# Arduino__Connectors.net
KiCad netlist of a schematic drawn in Altium Designer
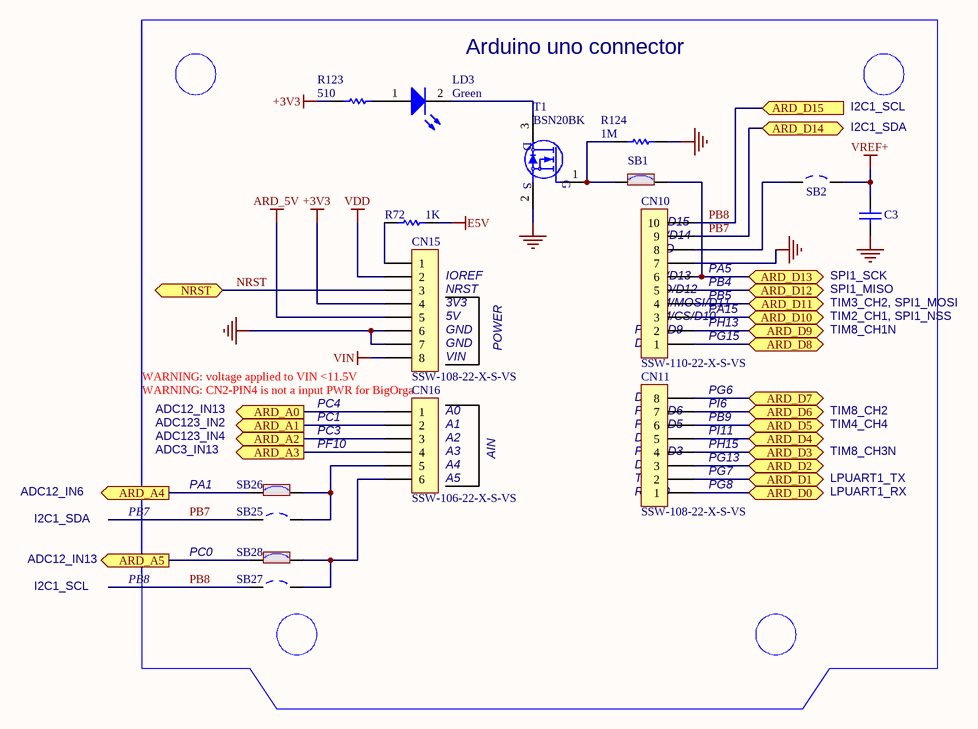
[diagram p0: Arduino_ Connectors.SchDoc]

(export (version "E")
  (design (tool "Eeschema 10.0.6"))
  (components
    (comp (ref "C3")
      (value "~")
      (footprint "0603C")
      (description "Capacitor,100nF,10%,16V,X7R,0603,YAGEO")
      (fields (field (name "PUBLISHER") "Altium Limited"))
      (libsource (lib "Miscellaneous Devices") (part "Cap"))
    )
    (comp (ref "CN10")
      (value "SSW-110-22-X-S-VS")
      (footprint "SSW-110-22-X-S-VS")
      (description "Header, 10-Pin, Single row,female")
      (fields (field (name "PUBLISHER") "Altium Limited"))
      (libsource (lib "Nucleo_64") (part "Header 10X1_Female"))
    )
    (comp (ref "CN11")
      (value "SSW-108-22-X-S-VS")
      (footprint "SSW-108-22-X-S-VS")
      (description "Header, 8-Pin, Single row,female")
      (fields (field (name "PUBLISHER") "Altium Limited"))
      (libsource (lib "Nucleo_64") (part "Header 8X1_Female"))
    )
    (comp (ref "CN15")
      (value "SSW-108-22-X-S-VS")
      (footprint "SSW-108-22-X-S-VS")
      (description "Header, 8-Pin, Single row,female")
      (fields (field (name "PUBLISHER") "Altium Limited"))
      (libsource (lib "") (part "Header 8X1_Female_1"))
    )
    (comp (ref "CN16")
      (value "SSW-106-22-X-S-VS")
      (footprint "SSW-106-22-X-S-VS")
      (description "Header, 6-Pin, Single row,female")
      (fields (field (name "PUBLISHER") "Altium Limited"))
      (libsource (lib "Nucleo_64") (part "Header 6X1_Female"))
    )
    (comp (ref "LD3")
      (value "19-213SY6C/S530-E2/TR8LED")
      (footprint "0603D")
      (description "LED,Green,0603")
      (fields (field (name "CORLOR") "Green") (field (name "PUBLISHER") "Altium Limited"))
      (libsource (lib "Miscellaneous Devices") (part "LED2"))
    )
    (comp (ref "R72")
      (value "1K")
      (footprint "0603R")
      (description "Resistor,1K,0603,1%")
      (fields (field (name "PUBLISHER") "Altium Limited"))
      (libsource (lib "Miscellaneous Devices") (part "res1"))
    )
    (comp (ref "R123")
      (value "510")
      (footprint "0603R")
      (description "Resistor, 510R , 0603,1%,YAGEO")
      (fields (field (name "Comment") "RC0603JR-07510RL") (field (name "PUBLISHER") "Altium Limited"))
      (libsource (lib "Miscellaneous Devices") (part "res1"))
    )
    (comp (ref "R124")
      (value "1M")
      (footprint "0603R")
      (description "Resistor, 1M , 0603")
      (fields (field (name "PUBLISHER") "Altium Limited"))
      (libsource (lib "Miscellaneous Devices") (part "res1"))
    )
    (comp (ref "SB1")
      (value "Solder Bridge ON")
      (footprint "SB_0603")
      (libsource (lib "MCD_TOOLS") (part "SB_ON"))
    )
    (comp (ref "SB2")
      (value "Solder Bridge OFF")
      (footprint "SB_0603")
      (libsource (lib "MCD_TOOLS") (part "SB_OFF"))
    )
    (comp (ref "SB25")
      (value "Solder Bridge OFF")
      (footprint "SB_0603")
      (libsource (lib "MCD_TOOLS") (part "SB_OFF"))
    )
    (comp (ref "SB26")
      (value "Solder Bridge ON")
      (footprint "SB_0603")
      (libsource (lib "MCD_TOOLS") (part "SB_ON"))
    )
    (comp (ref "SB27")
      (value "Solder Bridge OFF")
      (footprint "SB_0603")
      (libsource (lib "MCD_TOOLS") (part "SB_OFF"))
    )
    (comp (ref "SB28")
      (value "Solder Bridge ON")
      (footprint "SB_0603")
      (libsource (lib "MCD_TOOLS") (part "SB_ON"))
    )
    (comp (ref "T1") (value "BSN20BK") (footprint "SOT-23") (libsource (lib "MB525") (part "2N7000")))
  )
  (nets
    (net (code "1") (name "+3V3") (class "Default")
      (node (ref "CN15") (pin "4") (pinfunction "4_4") (pintype "passive"))
      (node (ref "R123") (pin "1") (pinfunction "1_1") (pintype "passive"))
    )
    (net (code "2") (name "/ARD_A0") (class "Default")
      (node (ref "CN16") (pin "1") (pinfunction "1_1") (pintype "passive"))
    )
    (net (code "3") (name "/ARD_A1") (class "Default")
      (node (ref "CN16") (pin "2") (pinfunction "2_2") (pintype "passive"))
    )
    (net (code "4") (name "/ARD_A2") (class "Default")
      (node (ref "CN16") (pin "3") (pinfunction "3_3") (pintype "passive"))
    )
    (net (code "5") (name "/ARD_A3") (class "Default")
      (node (ref "CN16") (pin "4") (pinfunction "4_4") (pintype "passive"))
    )
    (net (code "6") (name "/ARD_A4") (class "Default")
      (node (ref "SB26") (pin "1") (pinfunction "1_1") (pintype "passive"))
    )
    (net (code "7") (name "/ARD_A5") (class "Default")
      (node (ref "SB28") (pin "1") (pinfunction "1_1") (pintype "passive"))
    )
    (net (code "8") (name "/ARD_D0") (class "Default")
      (node (ref "CN11") (pin "1") (pinfunction "1_1") (pintype "passive"))
    )
    (net (code "9") (name "/ARD_D1") (class "Default")
      (node (ref "CN11") (pin "2") (pinfunction "2_2") (pintype "passive"))
    )
    (net (code "10") (name "/ARD_D2") (class "Default")
      (node (ref "CN11") (pin "3") (pinfunction "3_3") (pintype "passive"))
    )
    (net (code "11") (name "/ARD_D3") (class "Default")
      (node (ref "CN11") (pin "4") (pinfunction "4_4") (pintype "passive"))
    )
    (net (code "12") (name "/ARD_D4") (class "Default")
      (node (ref "CN11") (pin "5") (pinfunction "5_5") (pintype "passive"))
    )
    (net (code "13") (name "/ARD_D5") (class "Default")
      (node (ref "CN11") (pin "6") (pinfunction "6_6") (pintype "passive"))
    )
    (net (code "14") (name "/ARD_D6") (class "Default")
      (node (ref "CN11") (pin "7") (pinfunction "7_7") (pintype "passive"))
    )
    (net (code "15") (name "/ARD_D7") (class "Default")
      (node (ref "CN11") (pin "8") (pinfunction "8_8") (pintype "passive"))
    )
    (net (code "16") (name "/ARD_D8") (class "Default")
      (node (ref "CN10") (pin "1") (pinfunction "1_1") (pintype "passive"))
    )
    (net (code "17") (name "/ARD_D9") (class "Default")
      (node (ref "CN10") (pin "2") (pinfunction "2_2") (pintype "passive"))
    )
    (net (code "18") (name "/ARD_D10") (class "Default")
      (node (ref "CN10") (pin "3") (pinfunction "3_3") (pintype "passive"))
    )
    (net (code "19") (name "/ARD_D11") (class "Default")
      (node (ref "CN10") (pin "4") (pinfunction "4_4") (pintype "passive"))
    )
    (net (code "20") (name "/ARD_D12") (class "Default")
      (node (ref "CN10") (pin "5") (pinfunction "5_5") (pintype "passive"))
    )
    (net (code "21") (name "/ARD_D13") (class "Default")
      (node (ref "CN10") (pin "6") (pinfunction "6_6") (pintype "passive"))
      (node (ref "SB1") (pin "2") (pinfunction "2_2") (pintype "passive"))
    )
    (net (code "22") (name "/NRST") (class "Default")
      (node (ref "CN15") (pin "3") (pinfunction "3_3") (pintype "passive"))
    )
    (net (code "23") (name "/PB7") (class "Default")
      (node (ref "CN10") (pin "9") (pinfunction "9_9") (pintype "passive"))
      (node (ref "SB25") (pin "1") (pinfunction "1_1") (pintype "passive"))
    )
    (net (code "24") (name "/PB8") (class "Default")
      (node (ref "CN10") (pin "10") (pinfunction "10_10") (pintype "passive"))
      (node (ref "SB27") (pin "1") (pinfunction "1_1") (pintype "passive"))
    )
    (net (code "25") (name "ARD_5V") (class "Default")
      (node (ref "CN15") (pin "5") (pinfunction "5_5") (pintype "passive"))
    )
    (net (code "26") (name "E5V") (class "Default")
      (node (ref "R72") (pin "1") (pinfunction "1_1") (pintype "passive"))
    )
    (net (code "27") (name "GND") (class "Default")
      (node (ref "C3") (pin "2") (pinfunction "2_2") (pintype "passive"))
      (node (ref "CN10") (pin "7") (pinfunction "7_7") (pintype "passive"))
      (node (ref "CN15") (pin "6") (pinfunction "6_6") (pintype "passive"))
      (node (ref "CN15") (pin "7") (pinfunction "7_7") (pintype "passive"))
      (node (ref "R124") (pin "2") (pinfunction "2_2") (pintype "passive"))
      (node (ref "T1") (pin "2") (pinfunction "S_2") (pintype "passive"))
    )
    (net (code "28") (name "Net-(CN10-Pad8)") (class "Default")
      (node (ref "CN10") (pin "8") (pinfunction "8_8") (pintype "passive"))
      (node (ref "SB2") (pin "1") (pinfunction "1_1") (pintype "passive"))
    )
    (net (code "29") (name "Net-(CN15-Pad1)") (class "Default")
      (node (ref "CN15") (pin "1") (pinfunction "1_1") (pintype "passive"))
      (node (ref "R72") (pin "2") (pinfunction "2_2") (pintype "passive"))
    )
    (net (code "30") (name "Net-(CN16-Pad5)") (class "Default")
      (node (ref "CN16") (pin "5") (pinfunction "5_5") (pintype "passive"))
      (node (ref "SB25") (pin "2") (pinfunction "2_2") (pintype "passive"))
      (node (ref "SB26") (pin "2") (pinfunction "2_2") (pintype "passive"))
    )
    (net (code "31") (name "Net-(CN16-Pad6)") (class "Default")
      (node (ref "CN16") (pin "6") (pinfunction "6_6") (pintype "passive"))
      (node (ref "SB27") (pin "2") (pinfunction "2_2") (pintype "passive"))
      (node (ref "SB28") (pin "2") (pinfunction "2_2") (pintype "passive"))
    )
    (net (code "32") (name "Net-(LD3-A)") (class "Default")
      (node (ref "LD3") (pin "1") (pinfunction "A_1") (pintype "passive"))
      (node (ref "R123") (pin "2") (pinfunction "2_2") (pintype "passive"))
    )
    (net (code "33") (name "Net-(LD3-K)") (class "Default")
      (node (ref "LD3") (pin "2") (pinfunction "K_2") (pintype "passive"))
      (node (ref "T1") (pin "3") (pinfunction "D_3") (pintype "passive"))
    )
    (net (code "34") (name "Net-(T1-G)") (class "Default")
      (node (ref "R124") (pin "1") (pinfunction "1_1") (pintype "passive"))
      (node (ref "SB1") (pin "1") (pinfunction "1_1") (pintype "passive"))
      (node (ref "T1") (pin "1") (pinfunction "G_1") (pintype "passive"))
    )
    (net (code "35") (name "VDD") (class "Default")
      (node (ref "CN15") (pin "2") (pinfunction "2_2") (pintype "passive"))
    )
    (net (code "36") (name "VIN") (class "Default")
      (node (ref "CN15") (pin "8") (pinfunction "8_8") (pintype "passive"))
    )
    (net (code "37") (name "VREF+") (class "Default")
      (node (ref "C3") (pin "1") (pinfunction "1_1") (pintype "passive"))
      (node (ref "SB2") (pin "2") (pinfunction "2_2") (pintype "passive"))
    )
  )
)
